# sensorGateway.net
KiCad netlist of a schematic drawn in EAGLE
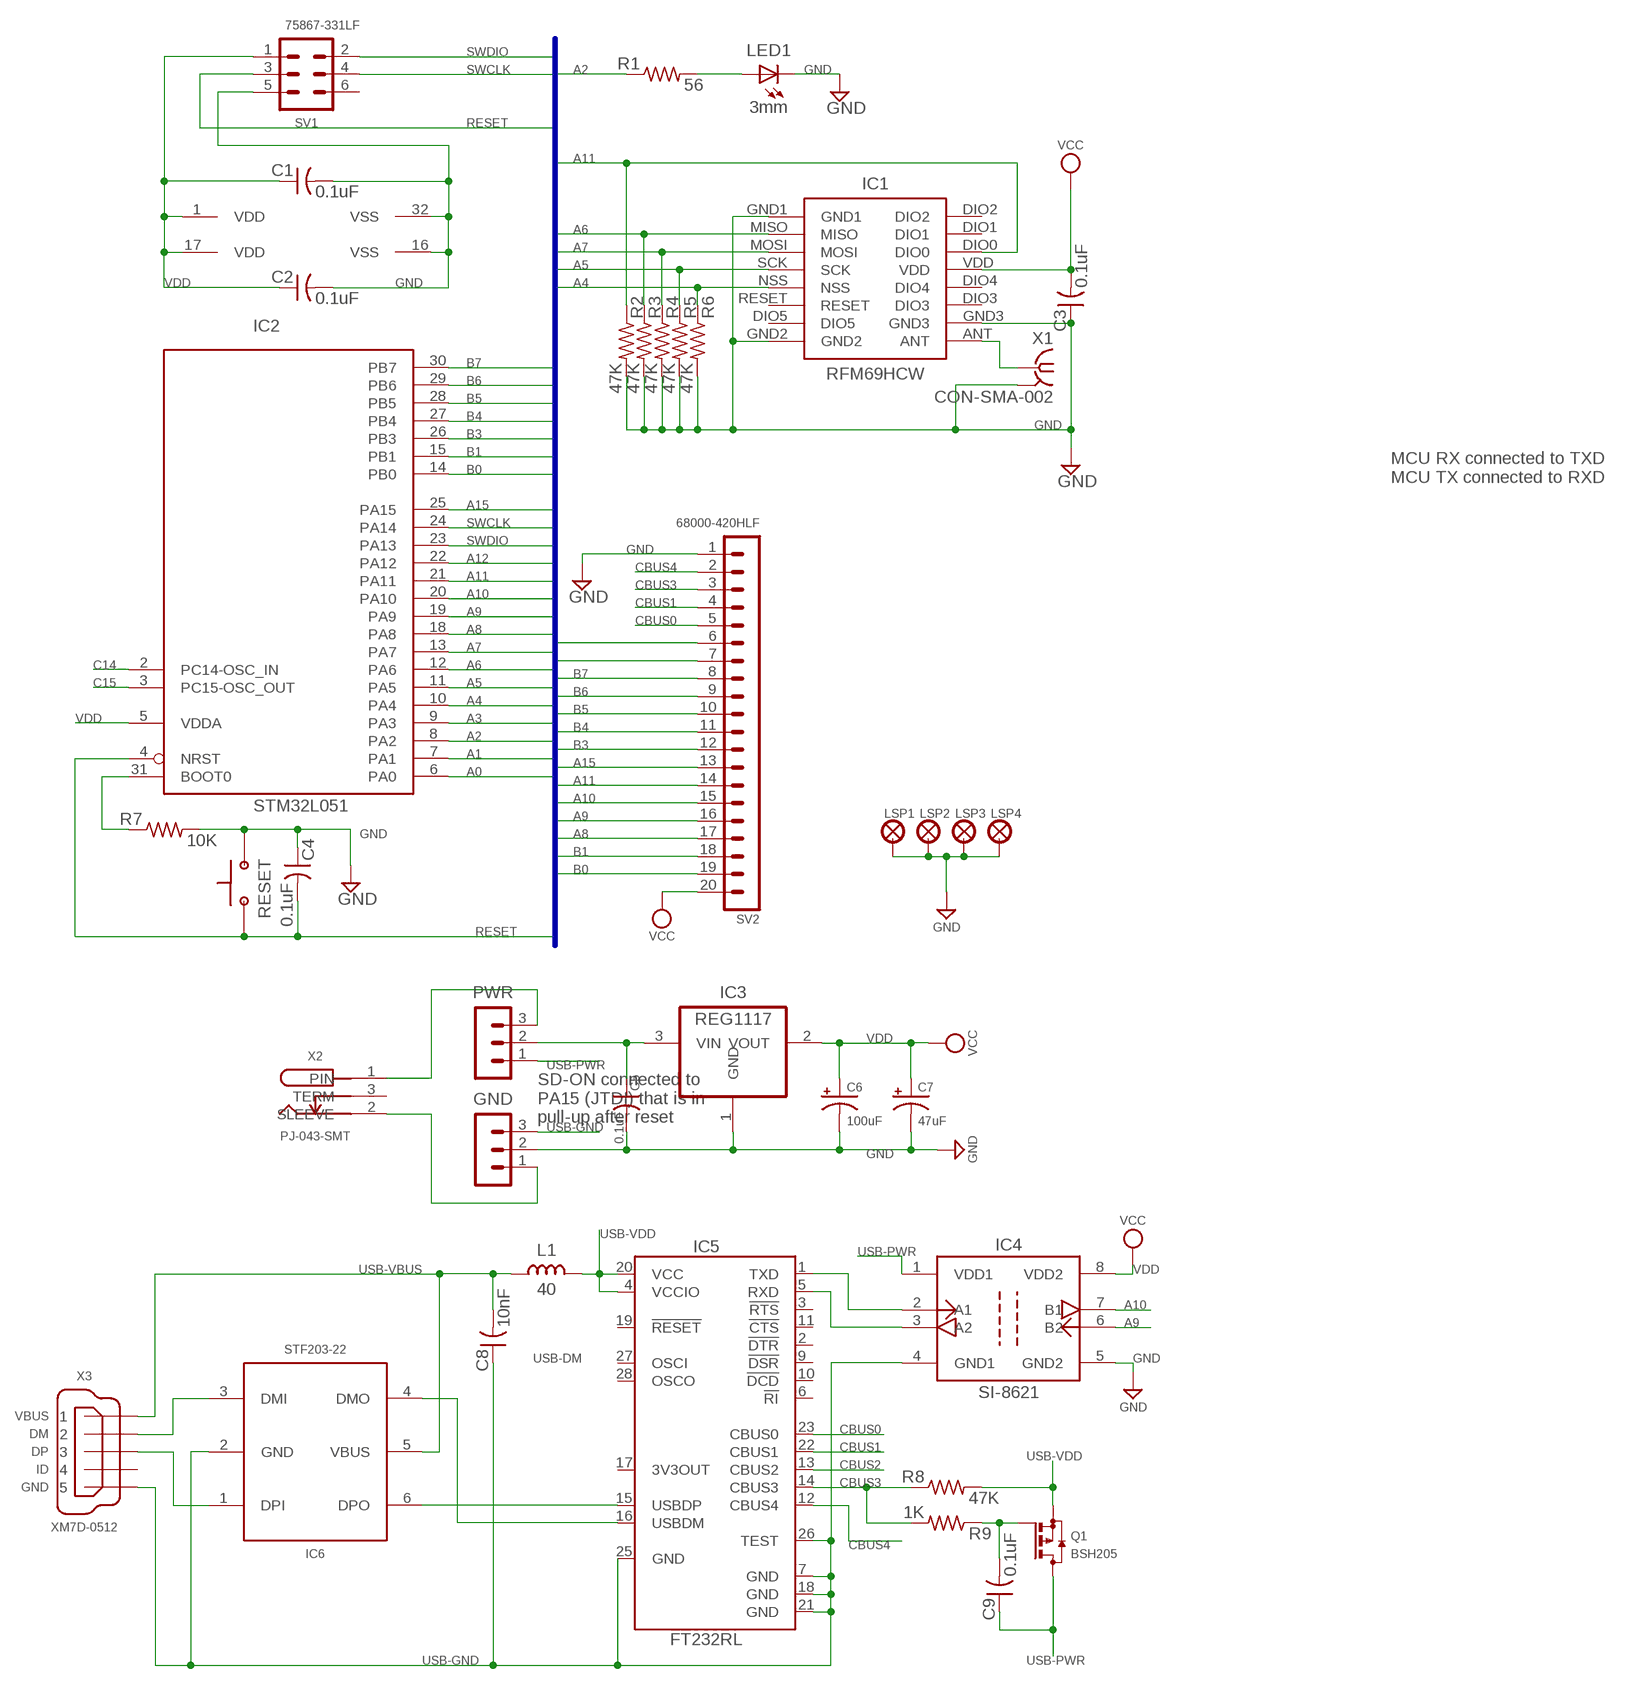
[diagram p0: schematic, sheet 1]

(export (version "E")
  (design (tool "Eeschema 10.0.6"))
  (components
    (comp (ref "C1")
      (value "0.1uF")
      (footprint "eagle-import:C0805")
      (libsource (lib "eagle-import") (part "C-US0805"))
    )
    (comp (ref "C2")
      (value "0.1uF")
      (footprint "eagle-import:C0805")
      (libsource (lib "eagle-import") (part "C-US0805"))
    )
    (comp (ref "C3")
      (value "0.1uF")
      (footprint "eagle-import:C0805")
      (libsource (lib "eagle-import") (part "C-US0805"))
    )
    (comp (ref "C4")
      (value "0.1uF")
      (footprint "eagle-import:C0805")
      (libsource (lib "eagle-import") (part "C-US0805"))
    )
    (comp (ref "C5")
      (value "0.1uF")
      (footprint "eagle-import:C0805")
      (libsource (lib "eagle-import") (part "C-US0805"))
    )
    (comp (ref "C6")
      (value "100uF")
      (footprint "eagle-import:CPOL1311")
      (libsource (lib "eagle-import") (part "CPOL-US1311"))
    )
    (comp (ref "C7")
      (value "47uF")
      (footprint "eagle-import:CPOL0805")
      (libsource (lib "eagle-import") (part "CPOL-US0805"))
    )
    (comp (ref "C8")
      (value "10nF")
      (footprint "eagle-import:C0805")
      (libsource (lib "eagle-import") (part "C-US0805"))
    )
    (comp (ref "C9")
      (value "0.1uF")
      (footprint "eagle-import:C0805")
      (libsource (lib "eagle-import") (part "C-US0805"))
    )
    (comp (ref "GND")
      (value "MA03-1PL")
      (footprint "eagle-import:MA03-1")
      (libsource (lib "eagle-import") (part "MA03-1PL"))
    )
    (comp (ref "IC1")
      (value "RFM69HCW")
      (footprint "eagle-import:RFM69HCW")
      (libsource (lib "eagle-import") (part "RFM69HCW"))
    )
    (comp (ref "IC2")
      (value "STM32L051")
      (footprint "eagle-import:LQFP32")
      (libsource (lib "eagle-import") (part "STM32L051KT8"))
    )
    (comp (ref "IC3")
      (value "REG1117")
      (footprint "eagle-import:SOT223")
      (libsource (lib "eagle-import") (part "REG1117"))
    )
    (comp (ref "IC4")
      (value "SI-8621")
      (footprint "eagle-import:SOIC-8")
      (libsource (lib "eagle-import") (part "SI-8621"))
    )
    (comp (ref "IC5")
      (value "FT232RL")
      (footprint "eagle-import:SSOP28")
      (libsource (lib "eagle-import") (part "FT232RL"))
    )
    (comp (ref "IC6")
      (value "STF203-22")
      (footprint "eagle-import:SC70-6")
      (libsource (lib "eagle-import") (part "STF203-22"))
    )
    (comp (ref "L1")
      (value "40")
      (footprint "eagle-import:L0805")
      (libsource (lib "eagle-import") (part "L-USL0805"))
    )
    (comp (ref "LED1")
      (value "3mm")
      (footprint "eagle-import:LED3MM")
      (libsource (lib "eagle-import") (part "LED3MM"))
    )
    (comp (ref "LSP1")
      (value "LSP27")
      (footprint "eagle-import:LSP27")
      (libsource (lib "eagle-import") (part "LSP27"))
    )
    (comp (ref "LSP2")
      (value "LSP27")
      (footprint "eagle-import:LSP27")
      (libsource (lib "eagle-import") (part "LSP27"))
    )
    (comp (ref "LSP3")
      (value "LSP27")
      (footprint "eagle-import:LSP27")
      (libsource (lib "eagle-import") (part "LSP27"))
    )
    (comp (ref "LSP4")
      (value "LSP27")
      (footprint "eagle-import:LSP27")
      (libsource (lib "eagle-import") (part "LSP27"))
    )
    (comp (ref "PWR")
      (value "MA03-1PL")
      (footprint "eagle-import:MA03-1")
      (libsource (lib "eagle-import") (part "MA03-1PL"))
    )
    (comp (ref "Q1")
      (value "BSH205")
      (footprint "eagle-import:SOT23")
      (libsource (lib "eagle-import") (part "BSH205G2R"))
    )
    (comp (ref "R1")
      (value "56")
      (footprint "eagle-import:R0805")
      (libsource (lib "eagle-import") (part "R-US0805"))
    )
    (comp (ref "R2")
      (value "47K")
      (footprint "eagle-import:R0805")
      (libsource (lib "eagle-import") (part "R-US0805"))
    )
    (comp (ref "R3")
      (value "47K")
      (footprint "eagle-import:R0805")
      (libsource (lib "eagle-import") (part "R-US0805"))
    )
    (comp (ref "R4")
      (value "47K")
      (footprint "eagle-import:R0805")
      (libsource (lib "eagle-import") (part "R-US0805"))
    )
    (comp (ref "R5")
      (value "47K")
      (footprint "eagle-import:R0805")
      (libsource (lib "eagle-import") (part "R-US0805"))
    )
    (comp (ref "R6")
      (value "47K")
      (footprint "eagle-import:R0805")
      (libsource (lib "eagle-import") (part "R-US0805"))
    )
    (comp (ref "R7")
      (value "10K")
      (footprint "eagle-import:R0805")
      (libsource (lib "eagle-import") (part "R-US0805"))
    )
    (comp (ref "R8")
      (value "47K")
      (footprint "eagle-import:R0805")
      (libsource (lib "eagle-import") (part "R-US0805"))
    )
    (comp (ref "R9")
      (value "1K")
      (footprint "eagle-import:R0805")
      (libsource (lib "eagle-import") (part "R-US0805"))
    )
    (comp (ref "RESET")
      (value "BUTTON-FSM14JRT")
      (footprint "eagle-import:BUTTON-FSM14JRT")
      (libsource (lib "eagle-import") (part "BUTTON-FSM14JRT"))
    )
    (comp (ref "SV1")
      (value "75867-331LF")
      (footprint "eagle-import:MA03-2")
      (libsource (lib "eagle-import") (part "MA03-2"))
    )
    (comp (ref "SV2")
      (value "68000-420HLF")
      (footprint "eagle-import:MA20-1-NO-PL")
      (libsource (lib "eagle-import") (part "MA20-1NO-PL"))
    )
    (comp (ref "X1")
      (value "CON-SMA-002")
      (footprint "eagle-import:BU-SMA-G")
      (libsource (lib "eagle-import") (part "BU-SMA-G"))
    )
    (comp (ref "X2")
      (value "PJ-043-SMT")
      (footprint "eagle-import:BUCHSE-1.0X3.2")
      (libsource (lib "eagle-import") (part "DC-POWER-JACK2"))
    )
    (comp (ref "X3")
      (value "XM7D-0512")
      (footprint "eagle-import:XM7D-0512")
      (libsource (lib "eagle-import") (part "MINI-USB-5-DPI"))
    )
  )
  (nets
    (net (code "1") (name "/A0") (class "Default")
      (node (ref "IC2") (pin "6") (pinfunction "PA0_6") (pintype "bidirectional"))
    )
    (net (code "2") (name "/A1") (class "Default")
      (node (ref "IC2") (pin "7") (pinfunction "PA1_7") (pintype "bidirectional"))
    )
    (net (code "3") (name "/A2") (class "Default")
      (node (ref "IC2") (pin "8") (pinfunction "PA2_8") (pintype "bidirectional"))
      (node (ref "R1") (pin "1") (pinfunction "1_1") (pintype "passive"))
    )
    (net (code "4") (name "/A3") (class "Default")
      (node (ref "IC2") (pin "9") (pinfunction "PA3_9") (pintype "bidirectional"))
    )
    (net (code "5") (name "/A4") (class "Default")
      (node (ref "IC1") (pin "NSS") (pinfunction "NSS_NSS") (pintype "bidirectional"))
      (node (ref "IC2") (pin "10") (pinfunction "PA4_10") (pintype "bidirectional"))
      (node (ref "R6") (pin "1") (pinfunction "1_1") (pintype "passive"))
    )
    (net (code "6") (name "/A5") (class "Default")
      (node (ref "IC1") (pin "SCK") (pinfunction "SCK_SCK") (pintype "bidirectional"))
      (node (ref "IC2") (pin "11") (pinfunction "PA5_11") (pintype "bidirectional"))
      (node (ref "R5") (pin "1") (pinfunction "1_1") (pintype "passive"))
    )
    (net (code "7") (name "/A6") (class "Default")
      (node (ref "IC1") (pin "MISO") (pinfunction "MISO_MISO") (pintype "bidirectional"))
      (node (ref "IC2") (pin "12") (pinfunction "PA6_12") (pintype "bidirectional"))
      (node (ref "R3") (pin "1") (pinfunction "1_1") (pintype "passive"))
    )
    (net (code "8") (name "/A7") (class "Default")
      (node (ref "IC1") (pin "MOSI") (pinfunction "MOSI_MOSI") (pintype "bidirectional"))
      (node (ref "IC2") (pin "13") (pinfunction "PA7_13") (pintype "bidirectional"))
      (node (ref "R4") (pin "1") (pinfunction "1_1") (pintype "passive"))
    )
    (net (code "9") (name "/A8") (class "Default")
      (node (ref "IC2") (pin "18") (pinfunction "PA8_18") (pintype "bidirectional"))
      (node (ref "SV2") (pin "17") (pinfunction "17_17") (pintype "passive"))
    )
    (net (code "10") (name "/A9") (class "Default")
      (node (ref "IC2") (pin "19") (pinfunction "PA9_19") (pintype "bidirectional"))
      (node (ref "IC4") (pin "6") (pinfunction "B2_6") (pintype "bidirectional"))
      (node (ref "SV2") (pin "16") (pinfunction "16_16") (pintype "passive"))
    )
    (net (code "11") (name "/A10") (class "Default")
      (node (ref "IC2") (pin "20") (pinfunction "PA10_20") (pintype "bidirectional"))
      (node (ref "IC4") (pin "7") (pinfunction "B1_7") (pintype "bidirectional"))
      (node (ref "SV2") (pin "15") (pinfunction "15_15") (pintype "passive"))
    )
    (net (code "12") (name "/A11") (class "Default")
      (node (ref "IC1") (pin "DIO0") (pinfunction "DIO0_DIO0") (pintype "bidirectional"))
      (node (ref "IC2") (pin "21") (pinfunction "PA11_21") (pintype "bidirectional"))
      (node (ref "R2") (pin "1") (pinfunction "1_1") (pintype "passive"))
      (node (ref "SV2") (pin "14") (pinfunction "14_14") (pintype "passive"))
    )
    (net (code "13") (name "/A12") (class "Default")
      (node (ref "IC2") (pin "22") (pinfunction "PA12_22") (pintype "bidirectional"))
    )
    (net (code "14") (name "/A15") (class "Default")
      (node (ref "IC2") (pin "25") (pinfunction "PA15_25") (pintype "bidirectional"))
      (node (ref "SV2") (pin "13") (pinfunction "13_13") (pintype "passive"))
    )
    (net (code "15") (name "/B0") (class "Default")
      (node (ref "IC2") (pin "14") (pinfunction "PB0_14") (pintype "bidirectional"))
      (node (ref "SV2") (pin "19") (pinfunction "19_19") (pintype "passive"))
    )
    (net (code "16") (name "/B1") (class "Default")
      (node (ref "IC2") (pin "15") (pinfunction "PB1_15") (pintype "bidirectional"))
      (node (ref "SV2") (pin "18") (pinfunction "18_18") (pintype "passive"))
    )
    (net (code "17") (name "/B3") (class "Default")
      (node (ref "IC2") (pin "26") (pinfunction "PB3_26") (pintype "bidirectional"))
      (node (ref "SV2") (pin "12") (pinfunction "12_12") (pintype "passive"))
    )
    (net (code "18") (name "/B4") (class "Default")
      (node (ref "IC2") (pin "27") (pinfunction "PB4_27") (pintype "bidirectional"))
      (node (ref "SV2") (pin "11") (pinfunction "11_11") (pintype "passive"))
    )
    (net (code "19") (name "/B5") (class "Default")
      (node (ref "IC2") (pin "28") (pinfunction "PB5_28") (pintype "bidirectional"))
      (node (ref "SV2") (pin "10") (pinfunction "10_10") (pintype "passive"))
    )
    (net (code "20") (name "/B6") (class "Default")
      (node (ref "IC2") (pin "29") (pinfunction "PB6_29") (pintype "bidirectional"))
      (node (ref "SV2") (pin "9") (pinfunction "9_9") (pintype "passive"))
    )
    (net (code "21") (name "/B7") (class "Default")
      (node (ref "IC2") (pin "30") (pinfunction "PB7_30") (pintype "bidirectional"))
      (node (ref "SV2") (pin "8") (pinfunction "8_8") (pintype "passive"))
    )
    (net (code "22") (name "/C14") (class "Default")
      (node (ref "IC2") (pin "2") (pinfunction "PC14-OSC_IN_2") (pintype "bidirectional"))
      (node (ref "SV2") (pin "7") (pinfunction "7_7") (pintype "passive"))
    )
    (net (code "23") (name "/C15") (class "Default")
      (node (ref "IC2") (pin "3") (pinfunction "PC15-OSC_OUT_3") (pintype "bidirectional"))
      (node (ref "SV2") (pin "6") (pinfunction "6_6") (pintype "passive"))
    )
    (net (code "24") (name "/CBUS0") (class "Default")
      (node (ref "IC5") (pin "23") (pinfunction "CBUS0_23") (pintype "bidirectional"))
      (node (ref "SV2") (pin "5") (pinfunction "5_5") (pintype "passive"))
    )
    (net (code "25") (name "/CBUS1") (class "Default")
      (node (ref "IC5") (pin "22") (pinfunction "CBUS1_22") (pintype "bidirectional"))
      (node (ref "SV2") (pin "4") (pinfunction "4_4") (pintype "passive"))
    )
    (net (code "26") (name "/CBUS2") (class "Default")
      (node (ref "IC5") (pin "13") (pinfunction "CBUS2_13") (pintype "bidirectional"))
    )
    (net (code "27") (name "/CBUS3") (class "Default")
      (node (ref "IC5") (pin "14") (pinfunction "CBUS3_14") (pintype "bidirectional"))
      (node (ref "R8") (pin "1") (pinfunction "1_1") (pintype "passive"))
      (node (ref "R9") (pin "2") (pinfunction "2_2") (pintype "passive"))
      (node (ref "SV2") (pin "3") (pinfunction "3_3") (pintype "passive"))
    )
    (net (code "28") (name "/CBUS4") (class "Default")
      (node (ref "IC5") (pin "12") (pinfunction "CBUS4_12") (pintype "bidirectional"))
      (node (ref "SV2") (pin "2") (pinfunction "2_2") (pintype "passive"))
    )
    (net (code "29") (name "/RESET") (class "Default")
      (node (ref "C4") (pin "2") (pinfunction "2_2") (pintype "passive"))
      (node (ref "IC2") (pin "4") (pinfunction "NRST_4") (pintype "bidirectional"))
      (node (ref "RESET") (pin "P$1") (pinfunction "1_P$1") (pintype "bidirectional"))
      (node (ref "SV1") (pin "3") (pinfunction "3_3") (pintype "passive"))
    )
    (net (code "30") (name "/SWCLK") (class "Default")
      (node (ref "IC2") (pin "24") (pinfunction "PA14_24") (pintype "bidirectional"))
      (node (ref "SV1") (pin "4") (pinfunction "4_4") (pintype "passive"))
    )
    (net (code "31") (name "/SWDIO") (class "Default")
      (node (ref "IC2") (pin "23") (pinfunction "PA13_23") (pintype "bidirectional"))
      (node (ref "SV1") (pin "2") (pinfunction "2_2") (pintype "passive"))
    )
    (net (code "32") (name "/USB-DM") (class "Default")
      (node (ref "IC5") (pin "16") (pinfunction "USBDM_16") (pintype "bidirectional"))
      (node (ref "IC6") (pin "4") (pinfunction "DMO_4") (pintype "bidirectional"))
    )
    (net (code "33") (name "/USB-GND") (class "Default")
      (node (ref "C8") (pin "1") (pinfunction "1_1") (pintype "passive"))
      (node (ref "GND") (pin "3") (pinfunction "3_3") (pintype "passive"))
      (node (ref "IC4") (pin "4") (pinfunction "GND1_4") (pintype "bidirectional"))
      (node (ref "IC5") (pin "18") (pinfunction "GND_18") (pintype "power_in"))
      (node (ref "IC5") (pin "21") (pinfunction "GND_21") (pintype "power_in"))
      (node (ref "IC5") (pin "25") (pinfunction "GND_25") (pintype "power_in"))
      (node (ref "IC5") (pin "26") (pinfunction "TEST_26") (pintype "input"))
      (node (ref "IC5") (pin "7") (pinfunction "GND_7") (pintype "power_in"))
      (node (ref "IC6") (pin "2") (pinfunction "GND_2") (pintype "bidirectional"))
      (node (ref "X3") (pin "5") (pinfunction "5_5") (pintype "passive"))
    )
    (net (code "34") (name "/USB-PWR") (class "Default")
      (node (ref "C9") (pin "1") (pinfunction "1_1") (pintype "passive"))
      (node (ref "IC4") (pin "1") (pinfunction "VDD1_1") (pintype "bidirectional"))
      (node (ref "PWR") (pin "1") (pinfunction "1_1") (pintype "passive"))
      (node (ref "Q1") (pin "3") (pinfunction "D_3") (pintype "passive"))
    )
    (net (code "35") (name "/USB-VBUS") (class "Default")
      (node (ref "C8") (pin "2") (pinfunction "2_2") (pintype "passive"))
      (node (ref "IC6") (pin "5") (pinfunction "VBUS_5") (pintype "bidirectional"))
      (node (ref "L1") (pin "1") (pinfunction "1_1") (pintype "passive"))
      (node (ref "X3") (pin "1") (pinfunction "1_1") (pintype "passive"))
    )
    (net (code "36") (name "/USB-VDD") (class "Default")
      (node (ref "IC5") (pin "20") (pinfunction "VCC_20") (pintype "power_in"))
      (node (ref "IC5") (pin "4") (pinfunction "VCCIO_4") (pintype "power_in"))
      (node (ref "L1") (pin "2") (pinfunction "2_2") (pintype "passive"))
      (node (ref "Q1") (pin "2") (pinfunction "S_2") (pintype "passive"))
      (node (ref "R8") (pin "2") (pinfunction "2_2") (pintype "passive"))
    )
    (net (code "37") (name "GND") (class "Default")
      (node (ref "C1") (pin "2") (pinfunction "2_2") (pintype "passive"))
      (node (ref "C2") (pin "2") (pinfunction "2_2") (pintype "passive"))
      (node (ref "C3") (pin "1") (pinfunction "1_1") (pintype "passive"))
      (node (ref "C4") (pin "1") (pinfunction "1_1") (pintype "passive"))
      (node (ref "C5") (pin "2") (pinfunction "2_2") (pintype "passive"))
      (node (ref "C6") (pin "2-") (pinfunction "-_2-") (pintype "passive"))
      (node (ref "C7") (pin "2-") (pinfunction "-_2-") (pintype "passive"))
      (node (ref "GND") (pin "2") (pinfunction "2_2") (pintype "passive"))
      (node (ref "IC1") (pin "GND1") (pinfunction "GND1_GND1") (pintype "bidirectional"))
      (node (ref "IC1") (pin "GND2") (pinfunction "GND2_GND2") (pintype "bidirectional"))
      (node (ref "IC1") (pin "GND3") (pinfunction "GND3_GND3") (pintype "bidirectional"))
      (node (ref "IC2") (pin "16") (pinfunction "VSS_16") (pintype "power_in"))
      (node (ref "IC2") (pin "32") (pinfunction "VSS_32") (pintype "power_in"))
      (node (ref "IC3") (pin "1") (pinfunction "GND_1") (pintype "power_in"))
      (node (ref "IC4") (pin "5") (pinfunction "GND2_5") (pintype "bidirectional"))
      (node (ref "LED1") (pin "K") (pinfunction "C_K") (pintype "passive"))
      (node (ref "LSP1") (pin "MP") (pinfunction "MP_MP") (pintype "passive"))
      (node (ref "LSP2") (pin "MP") (pinfunction "MP_MP") (pintype "passive"))
      (node (ref "LSP3") (pin "MP") (pinfunction "MP_MP") (pintype "passive"))
      (node (ref "LSP4") (pin "MP") (pinfunction "MP_MP") (pintype "passive"))
      (node (ref "R2") (pin "2") (pinfunction "2_2") (pintype "passive"))
      (node (ref "R3") (pin "2") (pinfunction "2_2") (pintype "passive"))
      (node (ref "R4") (pin "2") (pinfunction "2_2") (pintype "passive"))
      (node (ref "R5") (pin "2") (pinfunction "2_2") (pintype "passive"))
      (node (ref "R6") (pin "2") (pinfunction "2_2") (pintype "passive"))
      (node (ref "R7") (pin "2") (pinfunction "2_2") (pintype "passive"))
      (node (ref "RESET") (pin "P$2") (pinfunction "2_P$2") (pintype "bidirectional"))
      (node (ref "SV1") (pin "5") (pinfunction "5_5") (pintype "passive"))
      (node (ref "SV2") (pin "1") (pinfunction "1_1") (pintype "passive"))
      (node (ref "X1") (pin "2") (pinfunction "2_2") (pintype "passive"))
      (node (ref "X1") (pin "3") (pinfunction "2_3") (pintype "passive"))
      (node (ref "X1") (pin "4") (pinfunction "2_4") (pintype "passive"))
      (node (ref "X1") (pin "5") (pinfunction "2_5") (pintype "passive"))
    )
    (net (code "38") (name "Net-(IC1-PadANT)") (class "Default")
      (node (ref "IC1") (pin "ANT") (pinfunction "ANT_ANT") (pintype "bidirectional"))
      (node (ref "X1") (pin "1") (pinfunction "1_1") (pintype "passive"))
    )
    (net (code "39") (name "Net-(IC2A-BOOT0)") (class "Default")
      (node (ref "IC2") (pin "31") (pinfunction "BOOT0_31") (pintype "input"))
      (node (ref "R7") (pin "1") (pinfunction "1_1") (pintype "passive"))
    )
    (net (code "40") (name "Net-(IC3-VIN)") (class "Default")
      (node (ref "C5") (pin "1") (pinfunction "1_1") (pintype "passive"))
      (node (ref "IC3") (pin "3") (pinfunction "VIN_3") (pintype "input"))
      (node (ref "PWR") (pin "2") (pinfunction "2_2") (pintype "passive"))
    )
    (net (code "41") (name "Net-(IC4-A1)") (class "Default")
      (node (ref "IC4") (pin "2") (pinfunction "A1_2") (pintype "bidirectional"))
      (node (ref "IC5") (pin "1") (pinfunction "TXD_1") (pintype "output"))
    )
    (net (code "42") (name "Net-(IC4-A2)") (class "Default")
      (node (ref "IC4") (pin "3") (pinfunction "A2_3") (pintype "bidirectional"))
      (node (ref "IC5") (pin "5") (pinfunction "RXD_5") (pintype "input"))
    )
    (net (code "43") (name "Net-(IC5-USBDP)") (class "Default")
      (node (ref "IC5") (pin "15") (pinfunction "USBDP_15") (pintype "bidirectional"))
      (node (ref "IC6") (pin "6") (pinfunction "DPO_6") (pintype "bidirectional"))
    )
    (net (code "44") (name "Net-(IC6-DMI)") (class "Default")
      (node (ref "IC6") (pin "3") (pinfunction "DMI_3") (pintype "bidirectional"))
      (node (ref "X3") (pin "2") (pinfunction "2_2") (pintype "passive"))
    )
    (net (code "45") (name "Net-(IC6-DPI)") (class "Default")
      (node (ref "IC6") (pin "1") (pinfunction "DPI_1") (pintype "bidirectional"))
      (node (ref "X3") (pin "3") (pinfunction "3_3") (pintype "passive"))
    )
    (net (code "46") (name "Net-(LED1-PadA)") (class "Default")
      (node (ref "LED1") (pin "A") (pinfunction "A_A") (pintype "passive"))
      (node (ref "R1") (pin "2") (pinfunction "2_2") (pintype "passive"))
    )
    (net (code "47") (name "Net-(Q1-G)") (class "Default")
      (node (ref "C9") (pin "2") (pinfunction "2_2") (pintype "passive"))
      (node (ref "Q1") (pin "1") (pinfunction "G_1") (pintype "passive"))
      (node (ref "R9") (pin "1") (pinfunction "1_1") (pintype "passive"))
    )
    (net (code "48") (name "Net-(X2-PIN)") (class "Default")
      (node (ref "PWR") (pin "3") (pinfunction "3_3") (pintype "passive"))
      (node (ref "X2") (pin "1") (pinfunction "PIN_1") (pintype "power_in"))
    )
    (net (code "49") (name "Net-(X2-SLEEVE)") (class "Default")
      (node (ref "GND") (pin "1") (pinfunction "1_1") (pintype "passive"))
      (node (ref "X2") (pin "2") (pinfunction "SLEEVE_2") (pintype "power_in"))
    )
    (net (code "50") (name "VCC") (class "Default")
      (node (ref "C1") (pin "1") (pinfunction "1_1") (pintype "passive"))
      (node (ref "C2") (pin "1") (pinfunction "1_1") (pintype "passive"))
      (node (ref "C3") (pin "2") (pinfunction "2_2") (pintype "passive"))
      (node (ref "C6") (pin "1+") (pinfunction "+_1+") (pintype "passive"))
      (node (ref "C7") (pin "1+") (pinfunction "+_1+") (pintype "passive"))
      (node (ref "IC1") (pin "VDD") (pinfunction "VDD_VDD") (pintype "bidirectional"))
      (node (ref "IC2") (pin "1") (pinfunction "VDD_1") (pintype "power_in"))
      (node (ref "IC2") (pin "17") (pinfunction "VDD_17") (pintype "power_in"))
      (node (ref "IC2") (pin "5") (pinfunction "VDDA_5") (pintype "power_in"))
      (node (ref "IC3") (pin "2") (pinfunction "VOUT_2") (pintype "output"))
      (node (ref "IC4") (pin "8") (pinfunction "VDD2_8") (pintype "bidirectional"))
      (node (ref "SV1") (pin "1") (pinfunction "1_1") (pintype "passive"))
      (node (ref "SV2") (pin "20") (pinfunction "20_20") (pintype "passive"))
    )
    (net (code "51") (name "unconnected-(IC1-PadDIO1)") (class "Default")
      (node (ref "IC1") (pin "DIO1") (pinfunction "DIO1_DIO1") (pintype "bidirectional"))
    )
    (net (code "52") (name "unconnected-(IC1-PadDIO2)") (class "Default")
      (node (ref "IC1") (pin "DIO2") (pinfunction "DIO2_DIO2") (pintype "bidirectional"))
    )
    (net (code "53") (name "unconnected-(IC1-PadDIO3)") (class "Default")
      (node (ref "IC1") (pin "DIO3") (pinfunction "DIO3_DIO3") (pintype "bidirectional"))
    )
    (net (code "54") (name "unconnected-(IC1-PadDIO4)") (class "Default")
      (node (ref "IC1") (pin "DIO4") (pinfunction "DIO4_DIO4") (pintype "bidirectional"))
    )
    (net (code "55") (name "unconnected-(IC1-PadDIO5)") (class "Default")
      (node (ref "IC1") (pin "DIO5") (pinfunction "DIO5_DIO5") (pintype "bidirectional"))
    )
    (net (code "56") (name "unconnected-(IC1-PadRESET)") (class "Default")
      (node (ref "IC1") (pin "RESET") (pinfunction "RESET_RESET") (pintype "bidirectional"))
    )
    (net (code "57") (name "unconnected-(IC5-3V3OUT-Pad17)") (class "Default")
      (node (ref "IC5") (pin "17") (pinfunction "3V3OUT_17") (pintype "output"))
    )
    (net (code "58") (name "unconnected-(IC5-OSCI-Pad27)") (class "Default")
      (node (ref "IC5") (pin "27") (pinfunction "OSCI_27") (pintype "input"))
    )
    (net (code "59") (name "unconnected-(IC5-OSCO-Pad28)") (class "Default")
      (node (ref "IC5") (pin "28") (pinfunction "OSCO_28") (pintype "output"))
    )
    (net (code "60") (name "unconnected-(IC5-~{CTS}-Pad11)") (class "Default")
      (node (ref "IC5") (pin "11") (pinfunction "~{CTS}_11") (pintype "input"))
    )
    (net (code "61") (name "unconnected-(IC5-~{DCD}-Pad10)") (class "Default")
      (node (ref "IC5") (pin "10") (pinfunction "~{DCD}_10") (pintype "input"))
    )
    (net (code "62") (name "unconnected-(IC5-~{DSR}-Pad9)") (class "Default")
      (node (ref "IC5") (pin "9") (pinfunction "~{DSR}_9") (pintype "input"))
    )
    (net (code "63") (name "unconnected-(IC5-~{DTR}-Pad2)") (class "Default")
      (node (ref "IC5") (pin "2") (pinfunction "~{DTR}_2") (pintype "output"))
    )
    (net (code "64") (name "unconnected-(IC5-~{RESET}-Pad19)") (class "Default")
      (node (ref "IC5") (pin "19") (pinfunction "~{RESET}_19") (pintype "input"))
    )
    (net (code "65") (name "unconnected-(IC5-~{RI}-Pad6)") (class "Default")
      (node (ref "IC5") (pin "6") (pinfunction "~{RI}_6") (pintype "input"))
    )
    (net (code "66") (name "unconnected-(IC5-~{RTS}-Pad3)") (class "Default")
      (node (ref "IC5") (pin "3") (pinfunction "~{RTS}_3") (pintype "output"))
    )
    (net (code "67") (name "unconnected-(SV1-Pad6)") (class "Default")
      (node (ref "SV1") (pin "6") (pinfunction "6_6") (pintype "passive"))
    )
    (net (code "68") (name "unconnected-(X2-TERM-Pad3)") (class "Default")
      (node (ref "X2") (pin "3") (pinfunction "TERM_3") (pintype "bidirectional"))
    )
    (net (code "69") (name "unconnected-(X3-Pad4)") (class "Default")
      (node (ref "X3") (pin "4") (pinfunction "4_4") (pintype "passive"))
    )
  )
)
